# circuit.net
KiCad netlist of a schematic drawn in EAGLE
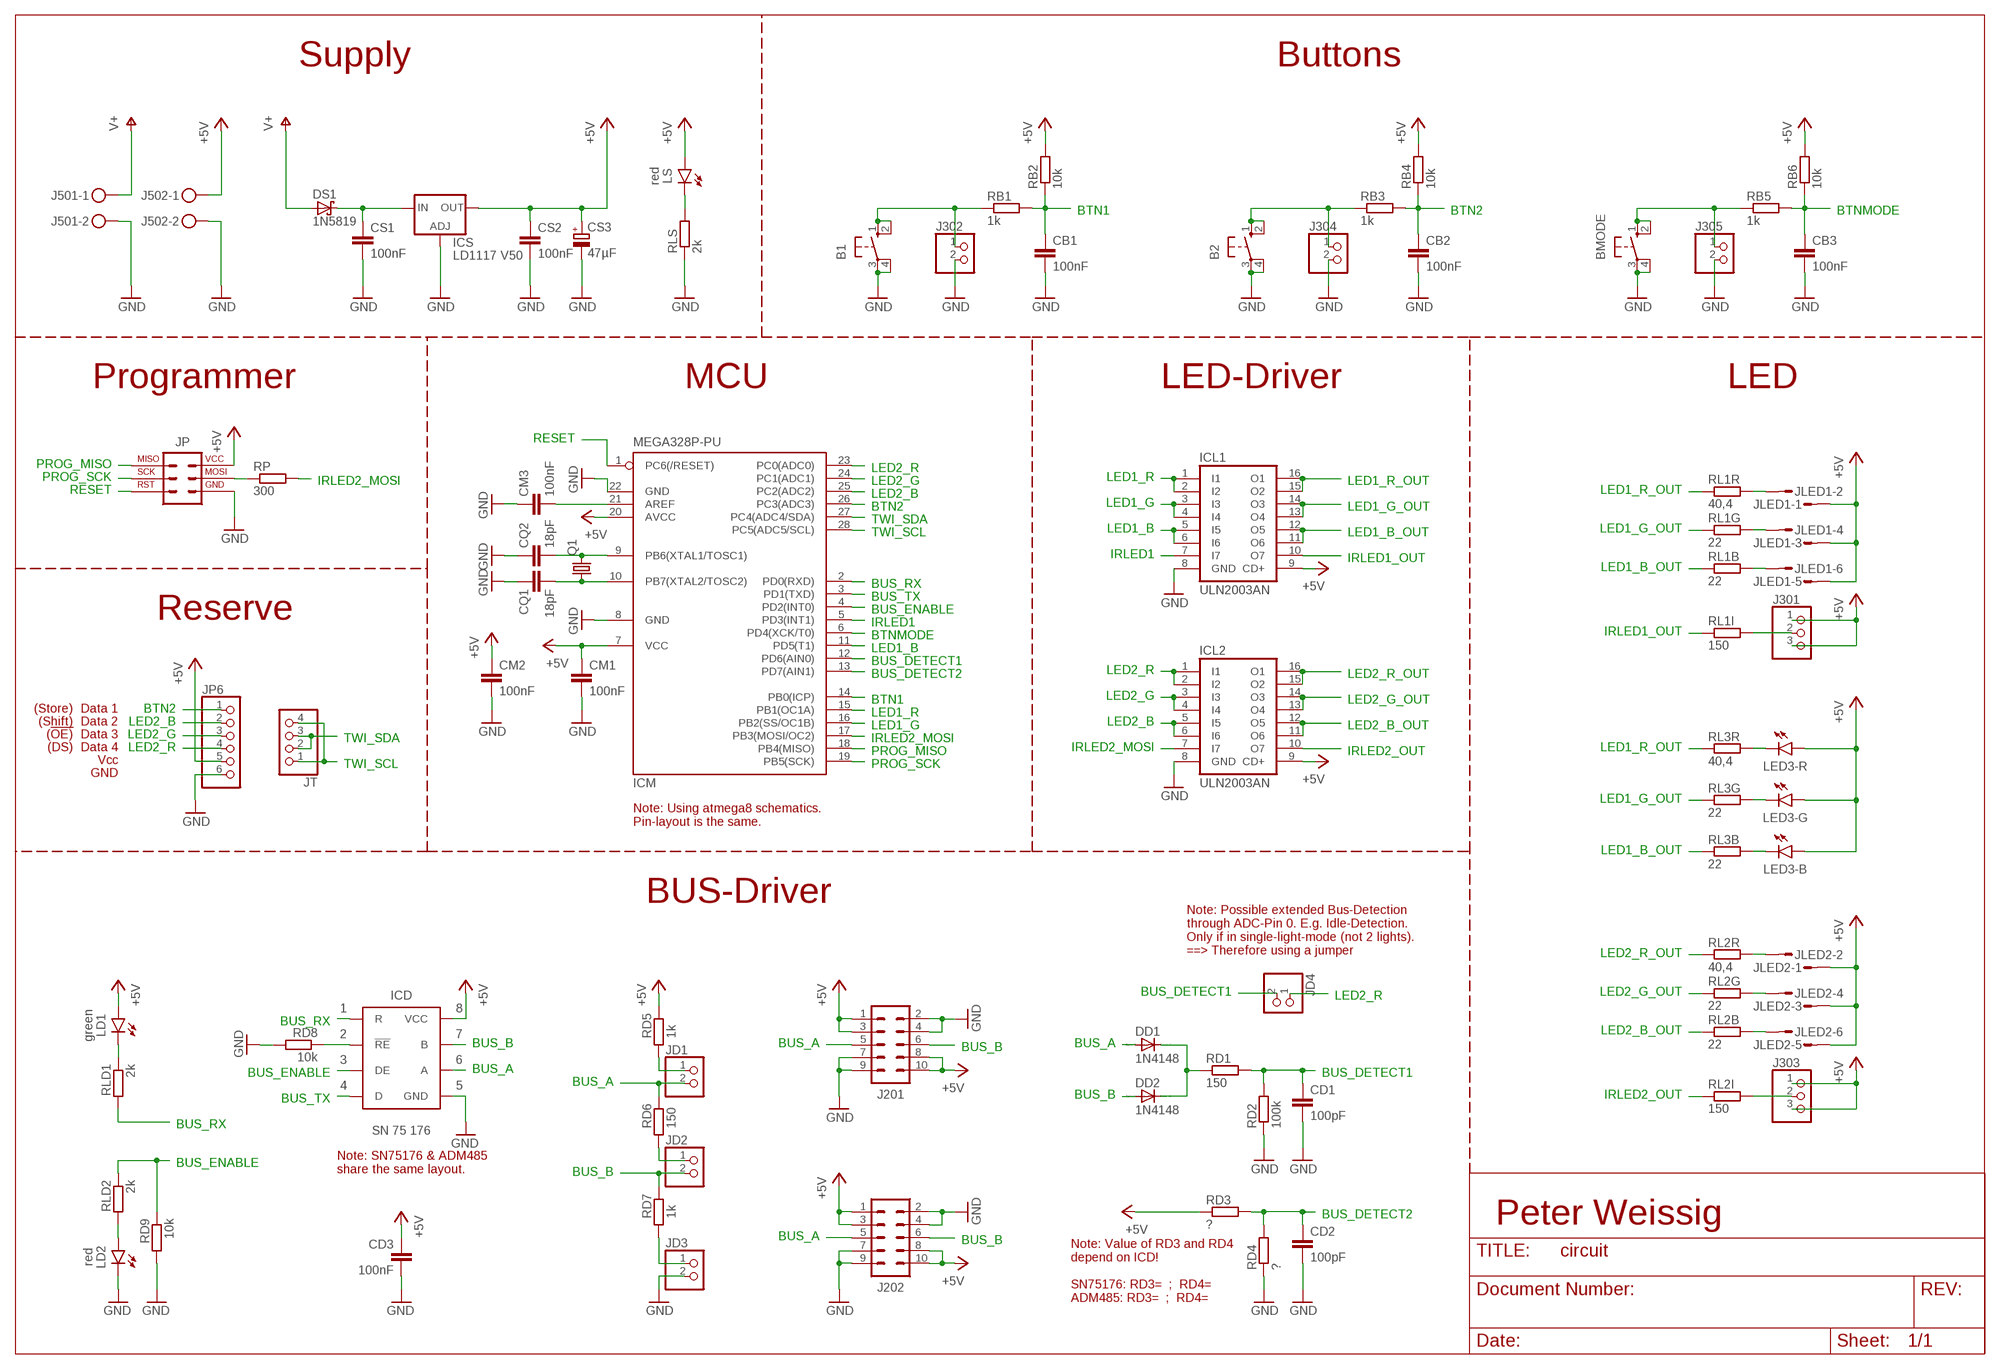
[diagram p0: schematic, sheet 1]

(export (version "E")
  (design (tool "Eeschema 10.0.6"))
  (components
    (comp (ref "B1")
      (value "10-XX")
      (footprint "eagle-import:B3F-10XX")
      (fields (field (name "MPN") "B3F-1000"))
      (libsource (lib "eagle-import") (part "10-XX"))
    )
    (comp (ref "B2")
      (value "10-XX")
      (footprint "eagle-import:B3F-10XX")
      (fields (field (name "MPN") "B3F-1000"))
      (libsource (lib "eagle-import") (part "10-XX"))
    )
    (comp (ref "BMODE")
      (value "10-XX")
      (footprint "eagle-import:B3F-10XX")
      (fields (field (name "MPN") "B3F-1000"))
      (libsource (lib "eagle-import") (part "10-XX"))
    )
    (comp (ref "CB1")
      (value "100nF")
      (footprint "eagle-import:C025-025X050")
      (libsource (lib "eagle-import") (part "C-EU025-025X050"))
    )
    (comp (ref "CB2")
      (value "100nF")
      (footprint "eagle-import:C025-025X050")
      (libsource (lib "eagle-import") (part "C-EU025-025X050"))
    )
    (comp (ref "CB3")
      (value "100nF")
      (footprint "eagle-import:C025-025X050")
      (libsource (lib "eagle-import") (part "C-EU025-025X050"))
    )
    (comp (ref "CD1")
      (value "100pF")
      (footprint "eagle-import:C025-025X050")
      (libsource (lib "eagle-import") (part "C-EU025-025X050"))
    )
    (comp (ref "CD2")
      (value "100pF")
      (footprint "eagle-import:C025-025X050")
      (libsource (lib "eagle-import") (part "C-EU025-025X050"))
    )
    (comp (ref "CD3")
      (value "100nF")
      (footprint "eagle-import:C025-025X050")
      (libsource (lib "eagle-import") (part "C-EU025-025X050"))
    )
    (comp (ref "CM1")
      (value "100nF")
      (footprint "eagle-import:C025-025X050")
      (libsource (lib "eagle-import") (part "C-EU025-025X050"))
    )
    (comp (ref "CM2")
      (value "100nF")
      (footprint "eagle-import:C025-025X050")
      (libsource (lib "eagle-import") (part "C-EU025-025X050"))
    )
    (comp (ref "CM3")
      (value "100nF")
      (footprint "eagle-import:C025-025X050")
      (libsource (lib "eagle-import") (part "C-EU025-025X050"))
    )
    (comp (ref "CQ1")
      (value "18pF")
      (footprint "eagle-import:C025-025X050")
      (libsource (lib "eagle-import") (part "C-EU025-025X050"))
    )
    (comp (ref "CQ2")
      (value "18pF")
      (footprint "eagle-import:C025-025X050")
      (libsource (lib "eagle-import") (part "C-EU025-025X050"))
    )
    (comp (ref "CS1")
      (value "100nF")
      (footprint "eagle-import:C025-025X050")
      (libsource (lib "eagle-import") (part "C-EU025-025X050"))
    )
    (comp (ref "CS2")
      (value "100nF")
      (footprint "eagle-import:C025-025X050")
      (libsource (lib "eagle-import") (part "C-EU025-025X050"))
    )
    (comp (ref "CS3")
      (value "47µF")
      (footprint "eagle-import:E2-5")
      (libsource (lib "eagle-import") (part "CPOL-EUE2-5"))
    )
    (comp (ref "DD1")
      (value "1N4148")
      (footprint "eagle-import:DO35-7")
      (libsource (lib "eagle-import") (part "1N4148DO35-7"))
    )
    (comp (ref "DD2")
      (value "1N4148")
      (footprint "eagle-import:DO35-7")
      (libsource (lib "eagle-import") (part "1N4148DO35-7"))
    )
    (comp (ref "DS1")
      (value "1N5819")
      (footprint "eagle-import:DO41-7.6")
      (libsource (lib "eagle-import") (part "1N5819-B"))
    )
    (comp (ref "ICD")
      (value "DRIVER_RS485")
      (footprint "eagle-import:IC_DIL08")
      (libsource (lib "eagle-import") (part "DRIVER_RS485"))
    )
    (comp (ref "ICL1")
      (value "ULN2003AN")
      (footprint "eagle-import:DIL16")
      (libsource (lib "eagle-import") (part "ULN2003AN"))
    )
    (comp (ref "ICL2")
      (value "ULN2003AN")
      (footprint "eagle-import:DIL16")
      (libsource (lib "eagle-import") (part "ULN2003AN"))
    )
    (comp (ref "ICM")
      (value "MEGA328P-PU")
      (footprint "eagle-import:DIL28-3")
      (libsource (lib "eagle-import") (part "MEGA8-P"))
    )
    (comp (ref "ICS")
      (value "LD1117 V50")
      (footprint "eagle-import:TO220L1")
      (libsource (lib "eagle-import") (part "LD117A?V50"))
    )
    (comp (ref "J201")
      (value "STECKER_WANNE_10")
      (footprint "eagle-import:STECKER_WANNE_10")
      (libsource (lib "eagle-import") (part "STECKER_WANNE_10"))
    )
    (comp (ref "J202")
      (value "STECKER_WANNE_10")
      (footprint "eagle-import:STECKER_WANNE_10")
      (libsource (lib "eagle-import") (part "STECKER_WANNE_10"))
    )
    (comp (ref "J301")
      (value "PINHD-1X3")
      (footprint "eagle-import:1X03")
      (libsource (lib "eagle-import") (part "PINHD-1X3"))
    )
    (comp (ref "J302")
      (value "PINHD-1X2")
      (footprint "eagle-import:1X02")
      (libsource (lib "eagle-import") (part "PINHD-1X2"))
    )
    (comp (ref "J303")
      (value "PINHD-1X3")
      (footprint "eagle-import:1X03")
      (libsource (lib "eagle-import") (part "PINHD-1X3"))
    )
    (comp (ref "J304")
      (value "PINHD-1X2")
      (footprint "eagle-import:1X02")
      (libsource (lib "eagle-import") (part "PINHD-1X2"))
    )
    (comp (ref "J305")
      (value "PINHD-1X2")
      (footprint "eagle-import:1X02")
      (libsource (lib "eagle-import") (part "PINHD-1X2"))
    )
    (comp (ref "J501")
      (value "STECKER_SPG_2")
      (footprint "eagle-import:STECKER_SPG_2")
      (libsource (lib "eagle-import") (part "STECKER_SPG_2"))
    )
    (comp (ref "J502")
      (value "STECKER_SPG_2")
      (footprint "eagle-import:STECKER_SPG_2")
      (libsource (lib "eagle-import") (part "STECKER_SPG_2"))
    )
    (comp (ref "JD1")
      (value "PINHD-1X2")
      (footprint "eagle-import:1X02")
      (libsource (lib "eagle-import") (part "PINHD-1X2"))
    )
    (comp (ref "JD2")
      (value "PINHD-1X2")
      (footprint "eagle-import:1X02")
      (libsource (lib "eagle-import") (part "PINHD-1X2"))
    )
    (comp (ref "JD3")
      (value "PINHD-1X2")
      (footprint "eagle-import:1X02")
      (libsource (lib "eagle-import") (part "PINHD-1X2"))
    )
    (comp (ref "JD4")
      (value "PINHD-1X2")
      (footprint "eagle-import:1X02")
      (libsource (lib "eagle-import") (part "PINHD-1X2"))
    )
    (comp (ref "JLED1")
      (value "MICROMATCH-6")
      (footprint "eagle-import:MICROMATCH-6")
      (fields (field (name "MPN") "7-215464-6"))
      (libsource (lib "eagle-import") (part "MICROMATCH-6"))
    )
    (comp (ref "JLED2")
      (value "MICROMATCH-6")
      (footprint "eagle-import:MICROMATCH-6")
      (fields (field (name "MPN") "7-215464-6"))
      (libsource (lib "eagle-import") (part "MICROMATCH-6"))
    )
    (comp (ref "JP")
      (value "STECKER_ISP_6")
      (footprint "eagle-import:STECKER_WANNE_6")
      (libsource (lib "eagle-import") (part "STECKER_ISP_6"))
    )
    (comp (ref "JP6")
      (value "PINHD-1X6/90")
      (footprint "eagle-import:1X06_90")
      (libsource (lib "eagle-import") (part "PINHD-1X6/90"))
    )
    (comp (ref "JT")
      (value "PINHD-1X4")
      (footprint "eagle-import:1X04")
      (libsource (lib "eagle-import") (part "PINHD-1X4"))
    )
    (comp (ref "LD1")
      (value "green")
      (footprint "eagle-import:LED_3MM")
      (libsource (lib "eagle-import") (part "LED-3MM"))
    )
    (comp (ref "LD2")
      (value "red")
      (footprint "eagle-import:LED_3MM")
      (libsource (lib "eagle-import") (part "LED-3MM"))
    )
    (comp (ref "LED3")
      (value "LED_3X")
      (footprint "eagle-import:LED_TOP_PLCC6")
      (libsource (lib "eagle-import") (part "LED_3X"))
    )
    (comp (ref "LS")
      (value "red")
      (footprint "eagle-import:LED_3MM")
      (libsource (lib "eagle-import") (part "LED-3MM"))
    )
    (comp (ref "Q1")
      (value "CRYSTALHC49U70")
      (footprint "eagle-import:HC49U70")
      (libsource (lib "eagle-import") (part "CRYSTALHC49U70"))
    )
    (comp (ref "RB1")
      (value "1k")
      (footprint "eagle-import:0207_10")
      (libsource (lib "eagle-import") (part "R-EU_0207/10"))
    )
    (comp (ref "RB2")
      (value "10k")
      (footprint "eagle-import:0207_10")
      (libsource (lib "eagle-import") (part "R-EU_0207/10"))
    )
    (comp (ref "RB3")
      (value "1k")
      (footprint "eagle-import:0207_10")
      (libsource (lib "eagle-import") (part "R-EU_0207/10"))
    )
    (comp (ref "RB4")
      (value "10k")
      (footprint "eagle-import:0207_10")
      (libsource (lib "eagle-import") (part "R-EU_0207/10"))
    )
    (comp (ref "RB5")
      (value "1k")
      (footprint "eagle-import:0207_10")
      (libsource (lib "eagle-import") (part "R-EU_0207/10"))
    )
    (comp (ref "RB6")
      (value "10k")
      (footprint "eagle-import:0207_10")
      (libsource (lib "eagle-import") (part "R-EU_0207/10"))
    )
    (comp (ref "RD1")
      (value "150")
      (footprint "eagle-import:0207_10")
      (libsource (lib "eagle-import") (part "R-EU_0207/10"))
    )
    (comp (ref "RD2")
      (value "100k")
      (footprint "eagle-import:0207_10")
      (libsource (lib "eagle-import") (part "R-EU_0207/10"))
    )
    (comp (ref "RD3")
      (value "?")
      (footprint "eagle-import:0207_10")
      (libsource (lib "eagle-import") (part "R-EU_0207/10"))
    )
    (comp (ref "RD4")
      (value "?")
      (footprint "eagle-import:0207_10")
      (libsource (lib "eagle-import") (part "R-EU_0207/10"))
    )
    (comp (ref "RD5")
      (value "1k")
      (footprint "eagle-import:0207_10")
      (libsource (lib "eagle-import") (part "R-EU_0207/10"))
    )
    (comp (ref "RD6")
      (value "150")
      (footprint "eagle-import:0207_10")
      (libsource (lib "eagle-import") (part "R-EU_0207/10"))
    )
    (comp (ref "RD7")
      (value "1k")
      (footprint "eagle-import:0207_10")
      (libsource (lib "eagle-import") (part "R-EU_0207/10"))
    )
    (comp (ref "RD8")
      (value "10k")
      (footprint "eagle-import:0207_10")
      (libsource (lib "eagle-import") (part "R-EU_0207/10"))
    )
    (comp (ref "RD9")
      (value "10k")
      (footprint "eagle-import:0207_10")
      (libsource (lib "eagle-import") (part "R-EU_0207/10"))
    )
    (comp (ref "RL1B")
      (value "22")
      (footprint "eagle-import:0207_10")
      (libsource (lib "eagle-import") (part "R-EU_0207/10"))
    )
    (comp (ref "RL1G")
      (value "22")
      (footprint "eagle-import:0207_10")
      (libsource (lib "eagle-import") (part "R-EU_0207/10"))
    )
    (comp (ref "RL1I")
      (value "150")
      (footprint "eagle-import:0207_10")
      (libsource (lib "eagle-import") (part "R-EU_0207/10"))
    )
    (comp (ref "RL1R")
      (value "40,4")
      (footprint "eagle-import:0207_10")
      (libsource (lib "eagle-import") (part "R-EU_0207/10"))
    )
    (comp (ref "RL2B")
      (value "22")
      (footprint "eagle-import:0207_10")
      (libsource (lib "eagle-import") (part "R-EU_0207/10"))
    )
    (comp (ref "RL2G")
      (value "22")
      (footprint "eagle-import:0207_10")
      (libsource (lib "eagle-import") (part "R-EU_0207/10"))
    )
    (comp (ref "RL2I")
      (value "150")
      (footprint "eagle-import:0207_10")
      (libsource (lib "eagle-import") (part "R-EU_0207/10"))
    )
    (comp (ref "RL2R")
      (value "40,4")
      (footprint "eagle-import:0207_10")
      (libsource (lib "eagle-import") (part "R-EU_0207/10"))
    )
    (comp (ref "RL3B")
      (value "22")
      (footprint "eagle-import:0207_10")
      (libsource (lib "eagle-import") (part "R-EU_0207/10"))
    )
    (comp (ref "RL3G")
      (value "22")
      (footprint "eagle-import:0207_10")
      (libsource (lib "eagle-import") (part "R-EU_0207/10"))
    )
    (comp (ref "RL3R")
      (value "40,4")
      (footprint "eagle-import:0207_10")
      (libsource (lib "eagle-import") (part "R-EU_0207/10"))
    )
    (comp (ref "RLD1")
      (value "2k")
      (footprint "eagle-import:0207_10")
      (libsource (lib "eagle-import") (part "R-EU_0207/10"))
    )
    (comp (ref "RLD2")
      (value "2k")
      (footprint "eagle-import:0207_10")
      (libsource (lib "eagle-import") (part "R-EU_0207/10"))
    )
    (comp (ref "RLS")
      (value "2k")
      (footprint "eagle-import:0207_10")
      (libsource (lib "eagle-import") (part "R-EU_0207/10"))
    )
    (comp (ref "RP")
      (value "300")
      (footprint "eagle-import:0207_10")
      (libsource (lib "eagle-import") (part "R-EU_0207/10"))
    )
  )
  (nets
    (net (code "1") (name "+5V") (class "Default")
      (node (ref "CD3") (pin "1") (pinfunction "1_1") (pintype "passive"))
      (node (ref "CM1") (pin "1") (pinfunction "1_1") (pintype "passive"))
      (node (ref "CM2") (pin "1") (pinfunction "1_1") (pintype "passive"))
      (node (ref "CS2") (pin "1") (pinfunction "1_1") (pintype "passive"))
      (node (ref "CS3") (pin "+") (pinfunction "+_+") (pintype "passive"))
      (node (ref "ICD") (pin "8") (pinfunction "VCC_8") (pintype "power_in"))
      (node (ref "ICL1") (pin "9") (pinfunction "CD+_9") (pintype "passive"))
      (node (ref "ICL2") (pin "9") (pinfunction "CD+_9") (pintype "passive"))
      (node (ref "ICM") (pin "20") (pinfunction "AVCC_20") (pintype "power_in"))
      (node (ref "ICM") (pin "7") (pinfunction "VCC_7") (pintype "power_in"))
      (node (ref "ICS") (pin "2") (pinfunction "OUT_2") (pintype "passive"))
      (node (ref "J201") (pin "1") (pinfunction "1_1") (pintype "passive"))
      (node (ref "J201") (pin "10") (pinfunction "10_10") (pintype "passive"))
      (node (ref "J201") (pin "3") (pinfunction "3_3") (pintype "passive"))
      (node (ref "J201") (pin "8") (pinfunction "8_8") (pintype "passive"))
      (node (ref "J202") (pin "1") (pinfunction "1_1") (pintype "passive"))
      (node (ref "J202") (pin "10") (pinfunction "10_10") (pintype "passive"))
      (node (ref "J202") (pin "3") (pinfunction "3_3") (pintype "passive"))
      (node (ref "J202") (pin "8") (pinfunction "8_8") (pintype "passive"))
      (node (ref "J301") (pin "1") (pinfunction "1_1") (pintype "passive"))
      (node (ref "J301") (pin "3") (pinfunction "3_3") (pintype "passive"))
      (node (ref "J303") (pin "1") (pinfunction "1_1") (pintype "passive"))
      (node (ref "J303") (pin "3") (pinfunction "3_3") (pintype "passive"))
      (node (ref "J502") (pin "1") (pinfunction "KL_1") (pintype "passive"))
      (node (ref "JLED1") (pin "1") (pinfunction "S_1") (pintype "passive"))
      (node (ref "JLED1") (pin "3") (pinfunction "S_3") (pintype "passive"))
      (node (ref "JLED1") (pin "5") (pinfunction "S_5") (pintype "passive"))
      (node (ref "JLED2") (pin "1") (pinfunction "S_1") (pintype "passive"))
      (node (ref "JLED2") (pin "3") (pinfunction "S_3") (pintype "passive"))
      (node (ref "JLED2") (pin "5") (pinfunction "S_5") (pintype "passive"))
      (node (ref "JP") (pin "2") (pinfunction "2_VCC_2") (pintype "passive"))
      (node (ref "JP6") (pin "5") (pinfunction "5_5") (pintype "passive"))
      (node (ref "LD1") (pin "A") (pinfunction "A_A") (pintype "passive"))
      (node (ref "LED3") (pin "1") (pinfunction "A_1") (pintype "passive"))
      (node (ref "LED3") (pin "3") (pinfunction "A_3") (pintype "passive"))
      (node (ref "LED3") (pin "4") (pinfunction "A_4") (pintype "passive"))
      (node (ref "LS") (pin "A") (pinfunction "A_A") (pintype "passive"))
      (node (ref "RB2") (pin "2") (pinfunction "2_2") (pintype "passive"))
      (node (ref "RB4") (pin "2") (pinfunction "2_2") (pintype "passive"))
      (node (ref "RB6") (pin "2") (pinfunction "2_2") (pintype "passive"))
      (node (ref "RD3") (pin "1") (pinfunction "1_1") (pintype "passive"))
      (node (ref "RD5") (pin "2") (pinfunction "2_2") (pintype "passive"))
    )
    (net (code "2") (name "/BTN1") (class "Default")
      (node (ref "CB1") (pin "1") (pinfunction "1_1") (pintype "passive"))
      (node (ref "ICM") (pin "14") (pinfunction "PB0(ICP)_14") (pintype "bidirectional"))
      (node (ref "RB1") (pin "2") (pinfunction "2_2") (pintype "passive"))
      (node (ref "RB2") (pin "1") (pinfunction "1_1") (pintype "passive"))
    )
    (net (code "3") (name "/BTN2") (class "Default")
      (node (ref "CB2") (pin "1") (pinfunction "1_1") (pintype "passive"))
      (node (ref "ICM") (pin "26") (pinfunction "PC3(ADC3)_26") (pintype "bidirectional"))
      (node (ref "JP6") (pin "1") (pinfunction "1_1") (pintype "passive"))
      (node (ref "RB3") (pin "2") (pinfunction "2_2") (pintype "passive"))
      (node (ref "RB4") (pin "1") (pinfunction "1_1") (pintype "passive"))
    )
    (net (code "4") (name "/BTNMODE") (class "Default")
      (node (ref "CB3") (pin "1") (pinfunction "1_1") (pintype "passive"))
      (node (ref "ICM") (pin "6") (pinfunction "PD4(XCK/T0)_6") (pintype "bidirectional"))
      (node (ref "RB5") (pin "2") (pinfunction "2_2") (pintype "passive"))
      (node (ref "RB6") (pin "1") (pinfunction "1_1") (pintype "passive"))
    )
    (net (code "5") (name "/BUS_A") (class "Default")
      (node (ref "DD1") (pin "A") (pinfunction "A_A") (pintype "passive"))
      (node (ref "ICD") (pin "6") (pinfunction "A_6") (pintype "bidirectional"))
      (node (ref "J201") (pin "5") (pinfunction "5_5") (pintype "passive"))
      (node (ref "J202") (pin "5") (pinfunction "5_5") (pintype "passive"))
      (node (ref "JD1") (pin "2") (pinfunction "2_2") (pintype "passive"))
      (node (ref "RD6") (pin "2") (pinfunction "2_2") (pintype "passive"))
    )
    (net (code "6") (name "/BUS_B") (class "Default")
      (node (ref "DD2") (pin "A") (pinfunction "A_A") (pintype "passive"))
      (node (ref "ICD") (pin "7") (pinfunction "B_7") (pintype "bidirectional"))
      (node (ref "J201") (pin "6") (pinfunction "6_6") (pintype "passive"))
      (node (ref "J202") (pin "6") (pinfunction "6_6") (pintype "passive"))
      (node (ref "JD2") (pin "2") (pinfunction "2_2") (pintype "passive"))
      (node (ref "RD7") (pin "2") (pinfunction "2_2") (pintype "passive"))
    )
    (net (code "7") (name "/BUS_DETECT1") (class "Default")
      (node (ref "CD1") (pin "1") (pinfunction "1_1") (pintype "passive"))
      (node (ref "ICM") (pin "12") (pinfunction "PD6(AIN0)_12") (pintype "bidirectional"))
      (node (ref "JD4") (pin "2") (pinfunction "2_2") (pintype "passive"))
      (node (ref "RD1") (pin "2") (pinfunction "2_2") (pintype "passive"))
      (node (ref "RD2") (pin "2") (pinfunction "2_2") (pintype "passive"))
    )
    (net (code "8") (name "/BUS_DETECT2") (class "Default")
      (node (ref "CD2") (pin "1") (pinfunction "1_1") (pintype "passive"))
      (node (ref "ICM") (pin "13") (pinfunction "PD7(AIN1)_13") (pintype "bidirectional"))
      (node (ref "RD3") (pin "2") (pinfunction "2_2") (pintype "passive"))
      (node (ref "RD4") (pin "2") (pinfunction "2_2") (pintype "passive"))
    )
    (net (code "9") (name "/BUS_ENABLE") (class "Default")
      (node (ref "ICD") (pin "3") (pinfunction "DE_3") (pintype "input"))
      (node (ref "ICM") (pin "4") (pinfunction "PD2(INT0)_4") (pintype "bidirectional"))
      (node (ref "RD9") (pin "1") (pinfunction "1_1") (pintype "passive"))
      (node (ref "RLD2") (pin "1") (pinfunction "1_1") (pintype "passive"))
    )
    (net (code "10") (name "/BUS_RX") (class "Default")
      (node (ref "ICD") (pin "1") (pinfunction "R_1") (pintype "output"))
      (node (ref "ICM") (pin "2") (pinfunction "PD0(RXD)_2") (pintype "bidirectional"))
      (node (ref "RLD1") (pin "2") (pinfunction "2_2") (pintype "passive"))
    )
    (net (code "11") (name "/BUS_TX") (class "Default")
      (node (ref "ICD") (pin "4") (pinfunction "D_4") (pintype "input"))
      (node (ref "ICM") (pin "3") (pinfunction "PD1(TXD)_3") (pintype "bidirectional"))
    )
    (net (code "12") (name "/IRLED1") (class "Default")
      (node (ref "ICL1") (pin "7") (pinfunction "I7_7") (pintype "input"))
      (node (ref "ICM") (pin "5") (pinfunction "PD3(INT1)_5") (pintype "bidirectional"))
    )
    (net (code "13") (name "/IRLED1_OUT") (class "Default")
      (node (ref "ICL1") (pin "10") (pinfunction "O7_10") (pintype "open_collector"))
      (node (ref "RL1I") (pin "1") (pinfunction "1_1") (pintype "passive"))
    )
    (net (code "14") (name "/IRLED2_MOSI") (class "Default")
      (node (ref "ICL2") (pin "7") (pinfunction "I7_7") (pintype "input"))
      (node (ref "ICM") (pin "17") (pinfunction "PB3(MOSI/OC2)_17") (pintype "bidirectional"))
      (node (ref "RP") (pin "2") (pinfunction "2_2") (pintype "passive"))
    )
    (net (code "15") (name "/IRLED2_OUT") (class "Default")
      (node (ref "ICL2") (pin "10") (pinfunction "O7_10") (pintype "open_collector"))
      (node (ref "RL2I") (pin "1") (pinfunction "1_1") (pintype "passive"))
    )
    (net (code "16") (name "/LED1_B") (class "Default")
      (node (ref "ICL1") (pin "5") (pinfunction "I5_5") (pintype "input"))
      (node (ref "ICL1") (pin "6") (pinfunction "I6_6") (pintype "input"))
      (node (ref "ICM") (pin "11") (pinfunction "PD5(T1)_11") (pintype "bidirectional"))
    )
    (net (code "17") (name "/LED1_B_OUT") (class "Default")
      (node (ref "ICL1") (pin "11") (pinfunction "O6_11") (pintype "open_collector"))
      (node (ref "ICL1") (pin "12") (pinfunction "O5_12") (pintype "open_collector"))
      (node (ref "RL1B") (pin "1") (pinfunction "1_1") (pintype "passive"))
      (node (ref "RL3B") (pin "1") (pinfunction "1_1") (pintype "passive"))
    )
    (net (code "18") (name "/LED1_G") (class "Default")
      (node (ref "ICL1") (pin "3") (pinfunction "I3_3") (pintype "input"))
      (node (ref "ICL1") (pin "4") (pinfunction "I4_4") (pintype "input"))
      (node (ref "ICM") (pin "16") (pinfunction "PB2(SS/OC1B)_16") (pintype "bidirectional"))
    )
    (net (code "19") (name "/LED1_G_OUT") (class "Default")
      (node (ref "ICL1") (pin "13") (pinfunction "O4_13") (pintype "open_collector"))
      (node (ref "ICL1") (pin "14") (pinfunction "O3_14") (pintype "open_collector"))
      (node (ref "RL1G") (pin "1") (pinfunction "1_1") (pintype "passive"))
      (node (ref "RL3G") (pin "1") (pinfunction "1_1") (pintype "passive"))
    )
    (net (code "20") (name "/LED1_R") (class "Default")
      (node (ref "ICL1") (pin "1") (pinfunction "I1_1") (pintype "input"))
      (node (ref "ICL1") (pin "2") (pinfunction "I2_2") (pintype "input"))
      (node (ref "ICM") (pin "15") (pinfunction "PB1(OC1A)_15") (pintype "bidirectional"))
    )
    (net (code "21") (name "/LED1_R_OUT") (class "Default")
      (node (ref "ICL1") (pin "15") (pinfunction "O2_15") (pintype "open_collector"))
      (node (ref "ICL1") (pin "16") (pinfunction "O1_16") (pintype "open_collector"))
      (node (ref "RL1R") (pin "1") (pinfunction "1_1") (pintype "passive"))
      (node (ref "RL3R") (pin "1") (pinfunction "1_1") (pintype "passive"))
    )
    (net (code "22") (name "/LED2_B") (class "Default")
      (node (ref "ICL2") (pin "5") (pinfunction "I5_5") (pintype "input"))
      (node (ref "ICL2") (pin "6") (pinfunction "I6_6") (pintype "input"))
      (node (ref "ICM") (pin "25") (pinfunction "PC2(ADC2)_25") (pintype "bidirectional"))
      (node (ref "JP6") (pin "2") (pinfunction "2_2") (pintype "passive"))
    )
    (net (code "23") (name "/LED2_B_OUT") (class "Default")
      (node (ref "ICL2") (pin "11") (pinfunction "O6_11") (pintype "open_collector"))
      (node (ref "ICL2") (pin "12") (pinfunction "O5_12") (pintype "open_collector"))
      (node (ref "RL2B") (pin "1") (pinfunction "1_1") (pintype "passive"))
    )
    (net (code "24") (name "/LED2_G") (class "Default")
      (node (ref "ICL2") (pin "3") (pinfunction "I3_3") (pintype "input"))
      (node (ref "ICL2") (pin "4") (pinfunction "I4_4") (pintype "input"))
      (node (ref "ICM") (pin "24") (pinfunction "PC1(ADC1)_24") (pintype "bidirectional"))
      (node (ref "JP6") (pin "3") (pinfunction "3_3") (pintype "passive"))
    )
    (net (code "25") (name "/LED2_G_OUT") (class "Default")
      (node (ref "ICL2") (pin "13") (pinfunction "O4_13") (pintype "open_collector"))
      (node (ref "ICL2") (pin "14") (pinfunction "O3_14") (pintype "open_collector"))
      (node (ref "RL2G") (pin "1") (pinfunction "1_1") (pintype "passive"))
    )
    (net (code "26") (name "/LED2_R") (class "Default")
      (node (ref "ICL2") (pin "1") (pinfunction "I1_1") (pintype "input"))
      (node (ref "ICL2") (pin "2") (pinfunction "I2_2") (pintype "input"))
      (node (ref "ICM") (pin "23") (pinfunction "PC0(ADC0)_23") (pintype "bidirectional"))
      (node (ref "JD4") (pin "1") (pinfunction "1_1") (pintype "passive"))
      (node (ref "JP6") (pin "4") (pinfunction "4_4") (pintype "passive"))
    )
    (net (code "27") (name "/LED2_R_OUT") (class "Default")
      (node (ref "ICL2") (pin "15") (pinfunction "O2_15") (pintype "open_collector"))
      (node (ref "ICL2") (pin "16") (pinfunction "O1_16") (pintype "open_collector"))
      (node (ref "RL2R") (pin "1") (pinfunction "1_1") (pintype "passive"))
    )
    (net (code "28") (name "/PROG_MISO") (class "Default")
      (node (ref "ICM") (pin "18") (pinfunction "PB4(MISO)_18") (pintype "bidirectional"))
      (node (ref "JP") (pin "1") (pinfunction "1_MISO_1") (pintype "passive"))
    )
    (net (code "29") (name "/PROG_SCK") (class "Default")
      (node (ref "ICM") (pin "19") (pinfunction "PB5(SCK)_19") (pintype "bidirectional"))
      (node (ref "JP") (pin "3") (pinfunction "3_SCK_3") (pintype "passive"))
    )
    (net (code "30") (name "/RESET") (class "Default")
      (node (ref "ICM") (pin "1") (pinfunction "PC6(/RESET)_1") (pintype "bidirectional"))
      (node (ref "JP") (pin "5") (pinfunction "5_RST_5") (pintype "passive"))
    )
    (net (code "31") (name "/TWI_SCL") (class "Default")
      (node (ref "ICM") (pin "28") (pinfunction "PC5(ADC5/SCL)_28") (pintype "bidirectional"))
      (node (ref "JT") (pin "1") (pinfunction "1_1") (pintype "passive"))
      (node (ref "JT") (pin "4") (pinfunction "4_4") (pintype "passive"))
    )
    (net (code "32") (name "/TWI_SDA") (class "Default")
      (node (ref "ICM") (pin "27") (pinfunction "PC4(ADC4/SDA)_27") (pintype "bidirectional"))
      (node (ref "JT") (pin "2") (pinfunction "2_2") (pintype "passive"))
      (node (ref "JT") (pin "3") (pinfunction "3_3") (pintype "passive"))
    )
    (net (code "33") (name "GND") (class "Default")
      (node (ref "B1") (pin "3") (pinfunction "P_3") (pintype "passive"))
      (node (ref "B1") (pin "4") (pinfunction "P1_4") (pintype "passive"))
      (node (ref "B2") (pin "3") (pinfunction "P_3") (pintype "passive"))
      (node (ref "B2") (pin "4") (pinfunction "P1_4") (pintype "passive"))
      (node (ref "BMODE") (pin "3") (pinfunction "P_3") (pintype "passive"))
      (node (ref "BMODE") (pin "4") (pinfunction "P1_4") (pintype "passive"))
      (node (ref "CB1") (pin "2") (pinfunction "2_2") (pintype "passive"))
      (node (ref "CB2") (pin "2") (pinfunction "2_2") (pintype "passive"))
      (node (ref "CB3") (pin "2") (pinfunction "2_2") (pintype "passive"))
      (node (ref "CD1") (pin "2") (pinfunction "2_2") (pintype "passive"))
      (node (ref "CD2") (pin "2") (pinfunction "2_2") (pintype "passive"))
      (node (ref "CD3") (pin "2") (pinfunction "2_2") (pintype "passive"))
      (node (ref "CM1") (pin "2") (pinfunction "2_2") (pintype "passive"))
      (node (ref "CM2") (pin "2") (pinfunction "2_2") (pintype "passive"))
      (node (ref "CM3") (pin "1") (pinfunction "1_1") (pintype "passive"))
      (node (ref "CQ1") (pin "1") (pinfunction "1_1") (pintype "passive"))
      (node (ref "CQ2") (pin "1") (pinfunction "1_1") (pintype "passive"))
      (node (ref "CS1") (pin "2") (pinfunction "2_2") (pintype "passive"))
      (node (ref "CS2") (pin "2") (pinfunction "2_2") (pintype "passive"))
      (node (ref "CS3") (pin "-") (pinfunction "-_-") (pintype "passive"))
      (node (ref "ICD") (pin "5") (pinfunction "GND_5") (pintype "power_in"))
      (node (ref "ICL1") (pin "8") (pinfunction "GND_8") (pintype "power_in"))
      (node (ref "ICL2") (pin "8") (pinfunction "GND_8") (pintype "power_in"))
      (node (ref "ICM") (pin "22") (pinfunction "GND_22") (pintype "power_in"))
      (node (ref "ICM") (pin "8") (pinfunction "GND_8") (pintype "power_in"))
      (node (ref "ICS") (pin "1") (pinfunction "ADJ_1") (pintype "input"))
      (node (ref "J201") (pin "2") (pinfunction "2_2") (pintype "passive"))
      (node (ref "J201") (pin "4") (pinfunction "4_4") (pintype "passive"))
      (node (ref "J201") (pin "7") (pinfunction "7_7") (pintype "passive"))
      (node (ref "J201") (pin "9") (pinfunction "9_9") (pintype "passive"))
      (node (ref "J202") (pin "2") (pinfunction "2_2") (pintype "passive"))
      (node (ref "J202") (pin "4") (pinfunction "4_4") (pintype "passive"))
      (node (ref "J202") (pin "7") (pinfunction "7_7") (pintype "passive"))
      (node (ref "J202") (pin "9") (pinfunction "9_9") (pintype "passive"))
      (node (ref "J302") (pin "2") (pinfunction "2_2") (pintype "passive"))
      (node (ref "J304") (pin "2") (pinfunction "2_2") (pintype "passive"))
      (node (ref "J305") (pin "2") (pinfunction "2_2") (pintype "passive"))
      (node (ref "J501") (pin "2") (pinfunction "KL_2") (pintype "passive"))
      (node (ref "J502") (pin "2") (pinfunction "KL_2") (pintype "passive"))
      (node (ref "JD3") (pin "2") (pinfunction "2_2") (pintype "passive"))
      (node (ref "JP") (pin "6") (pinfunction "6_GND_6") (pintype "passive"))
      (node (ref "JP6") (pin "6") (pinfunction "6_6") (pintype "passive"))
      (node (ref "LD2") (pin "K") (pinfunction "C_K") (pintype "passive"))
      (node (ref "RD2") (pin "1") (pinfunction "1_1") (pintype "passive"))
      (node (ref "RD4") (pin "1") (pinfunction "1_1") (pintype "passive"))
      (node (ref "RD8") (pin "2") (pinfunction "2_2") (pintype "passive"))
      (node (ref "RD9") (pin "2") (pinfunction "2_2") (pintype "passive"))
      (node (ref "RLS") (pin "1") (pinfunction "1_1") (pintype "passive"))
    )
    (net (code "34") (name "Net-(B1-S)") (class "Default")
      (node (ref "B1") (pin "1") (pinfunction "S_1") (pintype "passive"))
      (node (ref "B1") (pin "2") (pinfunction "S1_2") (pintype "passive"))
      (node (ref "J302") (pin "1") (pinfunction "1_1") (pintype "passive"))
      (node (ref "RB1") (pin "1") (pinfunction "1_1") (pintype "passive"))
    )
    (net (code "35") (name "Net-(B2-S)") (class "Default")
      (node (ref "B2") (pin "1") (pinfunction "S_1") (pintype "passive"))
      (node (ref "B2") (pin "2") (pinfunction "S1_2") (pintype "passive"))
      (node (ref "J304") (pin "1") (pinfunction "1_1") (pintype "passive"))
      (node (ref "RB3") (pin "1") (pinfunction "1_1") (pintype "passive"))
    )
    (net (code "36") (name "Net-(BMODE-S)") (class "Default")
      (node (ref "BMODE") (pin "1") (pinfunction "S_1") (pintype "passive"))
      (node (ref "BMODE") (pin "2") (pinfunction "S1_2") (pintype "passive"))
      (node (ref "J305") (pin "1") (pinfunction "1_1") (pintype "passive"))
      (node (ref "RB5") (pin "1") (pinfunction "1_1") (pintype "passive"))
    )
    (net (code "37") (name "Net-(DD1-PadC)") (class "Default")
      (node (ref "DD1") (pin "C") (pinfunction "C_C") (pintype "passive"))
      (node (ref "DD2") (pin "C") (pinfunction "C_C") (pintype "passive"))
      (node (ref "RD1") (pin "1") (pinfunction "1_1") (pintype "passive"))
    )
    (net (code "38") (name "Net-(ICD-~{RE})") (class "Default")
      (node (ref "ICD") (pin "2") (pinfunction "~{RE}_2") (pintype "input"))
      (node (ref "RD8") (pin "1") (pinfunction "1_1") (pintype "passive"))
    )
    (net (code "39") (name "Net-(ICM-AREF)") (class "Default")
      (node (ref "CM3") (pin "2") (pinfunction "2_2") (pintype "passive"))
      (node (ref "ICM") (pin "21") (pinfunction "AREF_21") (pintype "passive"))
    )
    (net (code "40") (name "Net-(ICM-PB6(XTAL1{slash}TOSC1))") (class "Default")
      (node (ref "CQ2") (pin "2") (pinfunction "2_2") (pintype "passive"))
      (node (ref "ICM") (pin "9") (pinfunction "PB6(XTAL1/TOSC1)_9") (pintype "bidirectional"))
      (node (ref "Q1") (pin "2") (pinfunction "2_2") (pintype "passive"))
    )
    (net (code "41") (name "Net-(ICM-PB7(XTAL2{slash}TOSC2))") (class "Default")
      (node (ref "CQ1") (pin "2") (pinfunction "2_2") (pintype "passive"))
      (node (ref "ICM") (pin "10") (pinfunction "PB7(XTAL2/TOSC2)_10") (pintype "bidirectional"))
      (node (ref "Q1") (pin "1") (pinfunction "1_1") (pintype "passive"))
    )
    (net (code "42") (name "Net-(ICS-IN)") (class "Default")
      (node (ref "CS1") (pin "1") (pinfunction "1_1") (pintype "passive"))
      (node (ref "DS1") (pin "C") (pinfunction "C_C") (pintype "passive"))
      (node (ref "ICS") (pin "3") (pinfunction "IN_3") (pintype "input"))
    )
    (net (code "43") (name "Net-(J301-Pad2)") (class "Default")
      (node (ref "J301") (pin "2") (pinfunction "2_2") (pintype "passive"))
      (node (ref "RL1I") (pin "2") (pinfunction "2_2") (pintype "passive"))
    )
    (net (code "44") (name "Net-(J303-Pad2)") (class "Default")
      (node (ref "J303") (pin "2") (pinfunction "2_2") (pintype "passive"))
      (node (ref "RL2I") (pin "2") (pinfunction "2_2") (pintype "passive"))
    )
    (net (code "45") (name "Net-(JD1-Pad1)") (class "Default")
      (node (ref "JD1") (pin "1") (pinfunction "1_1") (pintype "passive"))
      (node (ref "RD5") (pin "1") (pinfunction "1_1") (pintype "passive"))
    )
    (net (code "46") (name "Net-(JD2-Pad1)") (class "Default")
      (node (ref "JD2") (pin "1") (pinfunction "1_1") (pintype "passive"))
      (node (ref "RD6") (pin "1") (pinfunction "1_1") (pintype "passive"))
    )
    (net (code "47") (name "Net-(JD3-Pad1)") (class "Default")
      (node (ref "JD3") (pin "1") (pinfunction "1_1") (pintype "passive"))
      (node (ref "RD7") (pin "1") (pinfunction "1_1") (pintype "passive"))
    )
    (net (code "48") (name "Net-(JLED1B-S)") (class "Default")
      (node (ref "JLED1") (pin "2") (pinfunction "S_2") (pintype "passive"))
      (node (ref "RL1R") (pin "2") (pinfunction "2_2") (pintype "passive"))
    )
    (net (code "49") (name "Net-(JLED1D-S)") (class "Default")
      (node (ref "JLED1") (pin "4") (pinfunction "S_4") (pintype "passive"))
      (node (ref "RL1G") (pin "2") (pinfunction "2_2") (pintype "passive"))
    )
    (net (code "50") (name "Net-(JLED1F-S)") (class "Default")
      (node (ref "JLED1") (pin "6") (pinfunction "S_6") (pintype "passive"))
      (node (ref "RL1B") (pin "2") (pinfunction "2_2") (pintype "passive"))
    )
    (net (code "51") (name "Net-(JLED2B-S)") (class "Default")
      (node (ref "JLED2") (pin "2") (pinfunction "S_2") (pintype "passive"))
      (node (ref "RL2R") (pin "2") (pinfunction "2_2") (pintype "passive"))
    )
    (net (code "52") (name "Net-(JLED2D-S)") (class "Default")
      (node (ref "JLED2") (pin "4") (pinfunction "S_4") (pintype "passive"))
      (node (ref "RL2G") (pin "2") (pinfunction "2_2") (pintype "passive"))
    )
    (net (code "53") (name "Net-(JLED2F-S)") (class "Default")
      (node (ref "JLED2") (pin "6") (pinfunction "S_6") (pintype "passive"))
      (node (ref "RL2B") (pin "2") (pinfunction "2_2") (pintype "passive"))
    )
    (net (code "54") (name "Net-(JP-4_MOSI)") (class "Default")
      (node (ref "JP") (pin "4") (pinfunction "4_MOSI_4") (pintype "passive"))
      (node (ref "RP") (pin "1") (pinfunction "1_1") (pintype "passive"))
    )
    (net (code "55") (name "Net-(LD1-C)") (class "Default")
      (node (ref "LD1") (pin "K") (pinfunction "C_K") (pintype "passive"))
      (node (ref "RLD1") (pin "1") (pinfunction "1_1") (pintype "passive"))
    )
    (net (code "56") (name "Net-(LD2-PadA)") (class "Default")
      (node (ref "LD2") (pin "A") (pinfunction "A_A") (pintype "passive"))
      (node (ref "RLD2") (pin "2") (pinfunction "2_2") (pintype "passive"))
    )
    (net (code "57") (name "Net-(LED3A-C)") (class "Default")
      (node (ref "LED3") (pin "5") (pinfunction "C_5") (pintype "passive"))
      (node (ref "RL3B") (pin "2") (pinfunction "2_2") (pintype "passive"))
    )
    (net (code "58") (name "Net-(LED3B-C)") (class "Default")
      (node (ref "LED3") (pin "2") (pinfunction "C_2") (pintype "passive"))
      (node (ref "RL3G") (pin "2") (pinfunction "2_2") (pintype "passive"))
    )
    (net (code "59") (name "Net-(LED3C-C)") (class "Default")
      (node (ref "LED3") (pin "6") (pinfunction "C_6") (pintype "passive"))
      (node (ref "RL3R") (pin "2") (pinfunction "2_2") (pintype "passive"))
    )
    (net (code "60") (name "Net-(LS-C)") (class "Default")
      (node (ref "LS") (pin "K") (pinfunction "C_K") (pintype "passive"))
      (node (ref "RLS") (pin "2") (pinfunction "2_2") (pintype "passive"))
    )
    (net (code "61") (name "V+") (class "Default")
      (node (ref "DS1") (pin "A") (pinfunction "A_A") (pintype "passive"))
      (node (ref "J501") (pin "1") (pinfunction "KL_1") (pintype "passive"))
    )
  )
)
